# IC_Programmers.net
KiCad netlist of a schematic drawn in Altium Designer
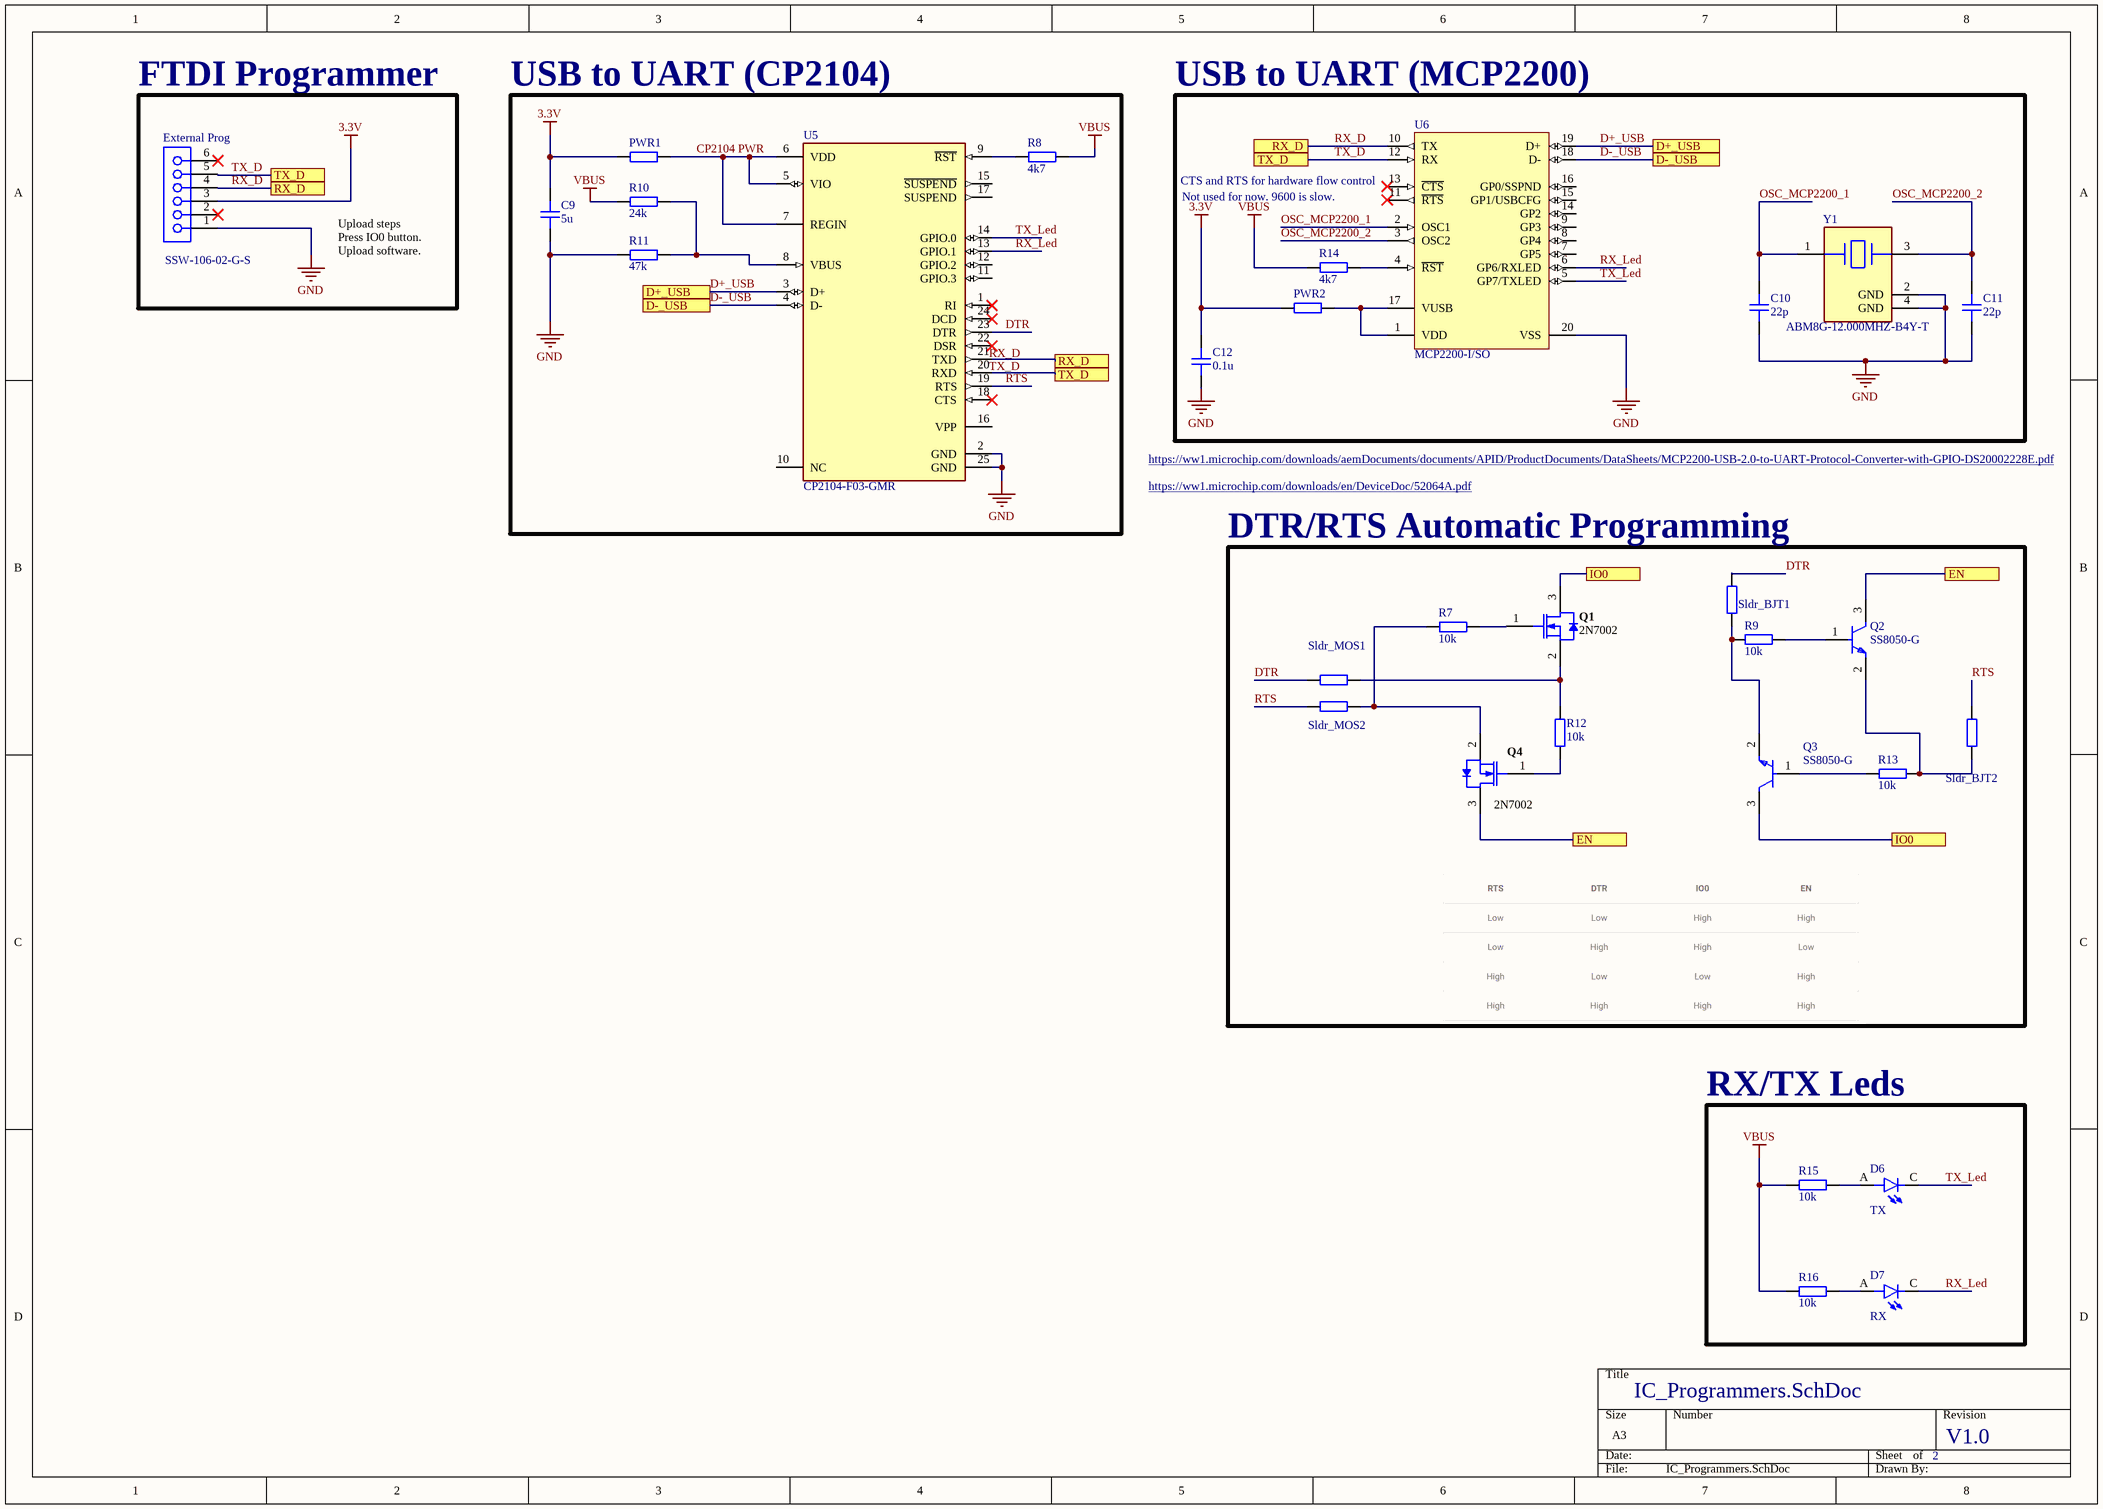
[diagram p0: IC_Programmers.SchDoc]

(export (version "E")
  (design (tool "Eeschema 10.0.6"))
  (components
    (comp (ref "C9")
      (value "5u")
      (footprint "CAP_1206")
      (description "Capacitor SMD 1206 50V")
      (libsource (lib "Schem_Lib_DaanHeetkamp.") (part "CAP_1206_50V"))
    )
    (comp (ref "C10")
      (value "22p")
      (footprint "CAP_1206")
      (description "Capacitor SMD 1206 50V")
      (libsource (lib "Schem_Lib_DaanHeetkamp.") (part "CAP_1206_50V"))
    )
    (comp (ref "C11")
      (value "22p")
      (footprint "CAP_1206")
      (description "Capacitor SMD 1206 50V")
      (libsource (lib "Schem_Lib_DaanHeetkamp.") (part "CAP_1206_50V"))
    )
    (comp (ref "C12")
      (value "0.1u")
      (footprint "CAP_1206")
      (description "Capacitor SMD 1206 50V")
      (libsource (lib "Schem_Lib_DaanHeetkamp.") (part "CAP_1206_50V"))
    )
    (comp (ref "D6")
      (value "TX")
      (footprint "PCB_Lib_DaanHeetkamp:LED_1206")
      (description "Yellow 587nm LED Indication - Discrete 2V 1206 _3216 Metric_")
      (fields (field (name "MF") "Lite-On Inc.") (field (name "MP") "LTST-C230KSKT"))
      (libsource (lib "Schem_Lib_DaanHeetkamp.") (part "LED - 1206"))
    )
    (comp (ref "D7")
      (value "RX")
      (footprint "PCB_Lib_DaanHeetkamp:LED_1206")
      (description "Yellow 587nm LED Indication - Discrete 2V 1206 _3216 Metric_")
      (fields (field (name "MF") "Lite-On Inc.") (field (name "MP") "LTST-C230KSKT"))
      (libsource (lib "Schem_Lib_DaanHeetkamp.") (part "LED - 1206"))
    )
    (comp (ref "External Prog")
      (value "SSW-106-02-G-S")
      (footprint "SMTC-SSW-106-02-X-S")
      (description "SQ Post Socket, Through-hole, Vertical, -55 to 125 degC, 2.54mm Pitch, 6-Pin, Female, RoHS")
      (fields (field (name "MANUFACTURER") "Samtec"))
      (libsource (lib "Altium Content Vault") (part "SMTC-SSW-106-02-X-S-X"))
    )
    (comp (ref "PWR1")
      (value "Solder Pin CP2104")
      (footprint "RES_1206")
      (description "Resistor SMD 1206")
      (libsource (lib "Schem_Lib_DaanHeetkamp.") (part "RES_1206"))
    )
    (comp (ref "PWR2")
      (value "Solder MCP2200")
      (footprint "RES_1206")
      (description "Resistor SMD 1206")
      (libsource (lib "Schem_Lib_DaanHeetkamp.") (part "RES_1206"))
    )
    (comp (ref "Q1")
      (value "2N7002")
      (footprint "INF-PG-SOT23_M")
      (fields (field (name "MANUFACTURER") "Infineon"))
      (libsource (lib "Altium Content Vault") (part "INF-NDMOS-GSD-3"))
    )
    (comp (ref "Q2")
      (value "SS8050-G")
      (footprint "FP-SS8050-G-MFG")
      (description "NPN TRANSISTOR 1.5A 40V SOT-23 R")
      (libsource (lib "Altium Content Vault") (part "2a1388f82443b098dcd57d24ac7632d"))
    )
    (comp (ref "Q3")
      (value "SS8050-G")
      (footprint "FP-SS8050-G-MFG")
      (description "NPN TRANSISTOR 1.5A 40V SOT-23 R")
      (libsource (lib "Altium Content Vault") (part "2a1388f82443b098dcd57d24ac7632d"))
    )
    (comp (ref "Q4")
      (value "2N7002")
      (footprint "INF-PG-SOT23_M")
      (fields (field (name "MANUFACTURER") "Infineon"))
      (libsource (lib "Altium Content Vault") (part "INF-NDMOS-GSD-3"))
    )
    (comp (ref "R7")
      (value "10k")
      (footprint "RES_1206")
      (description "Resistor SMD 1206")
      (libsource (lib "Schem_Lib_DaanHeetkamp.") (part "RES_1206"))
    )
    (comp (ref "R8")
      (value "4k7")
      (footprint "RES_1206")
      (description "Resistor SMD 1206")
      (libsource (lib "Schem_Lib_DaanHeetkamp.") (part "RES_1206"))
    )
    (comp (ref "R9")
      (value "10k")
      (footprint "RES_1206")
      (description "Resistor SMD 1206")
      (libsource (lib "Schem_Lib_DaanHeetkamp.") (part "RES_1206"))
    )
    (comp (ref "R10")
      (value "24k")
      (footprint "RES_1206")
      (description "Resistor SMD 1206")
      (libsource (lib "Schem_Lib_DaanHeetkamp.") (part "RES_1206"))
    )
    (comp (ref "R11")
      (value "47k")
      (footprint "RES_1206")
      (description "Resistor SMD 1206")
      (libsource (lib "Schem_Lib_DaanHeetkamp.") (part "RES_1206"))
    )
    (comp (ref "R12")
      (value "10k")
      (footprint "RES_1206")
      (description "Resistor SMD 1206")
      (libsource (lib "Schem_Lib_DaanHeetkamp.") (part "RES_1206"))
    )
    (comp (ref "R13")
      (value "10k")
      (footprint "RES_1206")
      (description "Resistor SMD 1206")
      (libsource (lib "Schem_Lib_DaanHeetkamp.") (part "RES_1206"))
    )
    (comp (ref "R14")
      (value "4k7")
      (footprint "RES_1206")
      (description "Resistor SMD 1206")
      (libsource (lib "Schem_Lib_DaanHeetkamp.") (part "RES_1206"))
    )
    (comp (ref "R15")
      (value "10k")
      (footprint "RES_1206")
      (description "Resistor SMD 1206")
      (libsource (lib "Schem_Lib_DaanHeetkamp.") (part "RES_1206"))
    )
    (comp (ref "R16")
      (value "10k")
      (footprint "RES_1206")
      (description "Resistor SMD 1206")
      (libsource (lib "Schem_Lib_DaanHeetkamp.") (part "RES_1206"))
    )
    (comp (ref "Sldr_BJT1")
      (value "R0603")
      (footprint "RES_0603")
      (description "Resistor SMD 0603")
      (libsource (lib "Schem_Lib_DaanHeetkamp.") (part "RES_0603"))
    )
    (comp (ref "Sldr_BJT2")
      (value "R0603")
      (footprint "RES_0603")
      (description "Resistor SMD 0603")
      (libsource (lib "Schem_Lib_DaanHeetkamp.") (part "RES_0603"))
    )
    (comp (ref "Sldr_MOS1")
      (value "R0603")
      (footprint "RES_0603")
      (description "Resistor SMD 0603")
      (libsource (lib "Schem_Lib_DaanHeetkamp.") (part "RES_0603"))
    )
    (comp (ref "Sldr_MOS2")
      (value "R0603")
      (footprint "RES_0603")
      (description "Resistor SMD 0603")
      (libsource (lib "Schem_Lib_DaanHeetkamp.") (part "RES_0603"))
    )
    (comp (ref "U5")
      (value "CP2104-F03-GMR")
      (footprint "FP-CP2104-F03-GMR-MFG")
      (description "IC SGL USB-TO-UART BRIDGE 24QFN")
      (fields
        (field (name "OCTOPART") "https://octopart.com/cp2104-f03-gmr-silicon+labs-19668642")
        (field (name "MANUFACTURER") "Silicon Laboratories")
      )
      (libsource (lib "Altium Content Vault") (part "c264a613fa4ce846ece45e07ca4b292"))
    )
    (comp (ref "U6")
      (value "MCP2200-I/SO")
      (footprint "SOIC-SO20_M")
      (description "USB 2.0 to UART Protocol Converter with GPIO, 20-Pin SOIC, Industrial Temperature")
      (libsource (lib "Altium Content Vault") (part "COM-USB-MCP2200-20"))
    )
    (comp (ref "Y1")
      (value "ABM8G-12.000MHZ-B4Y-T")
      (footprint "FP-ABM8G-MFG")
      (description "Crystal 12MHz ±30ppm (Tol) ±30ppm (Stability) 10pF FUND 120Ω 4-Pin SMD T/R")
      (fields (field (name "TOLERANCE") "30ppm"))
      (libsource (lib "Altium Content Vault") (part "48e526d86b7f2615d98721063c72f49"))
    )
  )
  (nets
    (net (code "1") (name "/CP2104 PWR") (class "Default")
      (node (ref "PWR1") (pin "2") (pinfunction "2_2") (pintype "passive"))
      (node (ref "U5") (pin "5") (pinfunction "VIO_5") (pintype "bidirectional"))
      (node (ref "U5") (pin "6") (pinfunction "VDD_6") (pintype "power_in"))
      (node (ref "U5") (pin "7") (pinfunction "REGIN_7") (pintype "power_in"))
    )
    (net (code "2") (name "/D+_USB") (class "Default")
      (node (ref "U5") (pin "3") (pinfunction "D+_3") (pintype "bidirectional"))
      (node (ref "U6") (pin "19") (pinfunction "D+_19") (pintype "bidirectional"))
    )
    (net (code "3") (name "/D-_USB") (class "Default")
      (node (ref "U5") (pin "4") (pinfunction "D-_4") (pintype "bidirectional"))
      (node (ref "U6") (pin "18") (pinfunction "D-_18") (pintype "bidirectional"))
    )
    (net (code "4") (name "/DTR") (class "Default")
      (node (ref "Sldr_BJT1") (pin "2") (pinfunction "2_2") (pintype "passive"))
      (node (ref "Sldr_MOS1") (pin "2") (pinfunction "2_2") (pintype "passive"))
      (node (ref "U5") (pin "23") (pinfunction "DTR_23") (pintype "output"))
    )
    (net (code "5") (name "/EN") (class "Default")
      (node (ref "Q2") (pin "3") (pinfunction "C_3") (pintype "passive"))
      (node (ref "Q4") (pin "3") (pinfunction "DRAIN_3") (pintype "passive"))
    )
    (net (code "6") (name "/IO0") (class "Default")
      (node (ref "Q1") (pin "3") (pinfunction "DRAIN_3") (pintype "passive"))
      (node (ref "Q3") (pin "3") (pinfunction "C_3") (pintype "passive"))
    )
    (net (code "7") (name "/OSC_MCP2200_1") (class "Default")
      (node (ref "C10") (pin "2") (pinfunction "2_2") (pintype "passive"))
      (node (ref "U6") (pin "2") (pinfunction "OSC1_2") (pintype "input"))
      (node (ref "Y1") (pin "1") (pinfunction "1_1") (pintype "passive"))
    )
    (net (code "8") (name "/OSC_MCP2200_2") (class "Default")
      (node (ref "C11") (pin "2") (pinfunction "2_2") (pintype "passive"))
      (node (ref "U6") (pin "3") (pinfunction "OSC2_3") (pintype "output"))
      (node (ref "Y1") (pin "3") (pinfunction "3_3") (pintype "passive"))
    )
    (net (code "9") (name "/RTS") (class "Default")
      (node (ref "Sldr_BJT2") (pin "2") (pinfunction "2_2") (pintype "passive"))
      (node (ref "Sldr_MOS2") (pin "2") (pinfunction "2_2") (pintype "passive"))
      (node (ref "U5") (pin "19") (pinfunction "RTS_19") (pintype "output"))
    )
    (net (code "10") (name "/RX_D") (class "Default")
      (node (ref "External Prog") (pin "4") (pinfunction "4_4") (pintype "passive"))
      (node (ref "U5") (pin "21") (pinfunction "TXD_21") (pintype "output"))
      (node (ref "U6") (pin "10") (pinfunction "TX_10") (pintype "output"))
    )
    (net (code "11") (name "/RX_Led") (class "Default")
      (node (ref "D7") (pin "C") (pinfunction "C_C") (pintype "passive"))
      (node (ref "U5") (pin "13") (pinfunction "GPIO.1_13") (pintype "bidirectional"))
      (node (ref "U6") (pin "6") (pinfunction "GP6/RXLED_6") (pintype "bidirectional"))
    )
    (net (code "12") (name "/TX_D") (class "Default")
      (node (ref "External Prog") (pin "5") (pinfunction "5_5") (pintype "passive"))
      (node (ref "U5") (pin "20") (pinfunction "RXD_20") (pintype "input"))
      (node (ref "U6") (pin "12") (pinfunction "RX_12") (pintype "input"))
    )
    (net (code "13") (name "/TX_Led") (class "Default")
      (node (ref "D6") (pin "C") (pinfunction "C_C") (pintype "passive"))
      (node (ref "U5") (pin "14") (pinfunction "GPIO.0_14") (pintype "bidirectional"))
      (node (ref "U6") (pin "5") (pinfunction "GP7/TXLED_5") (pintype "bidirectional"))
    )
    (net (code "14") (name "3.3V") (class "Default")
      (node (ref "C12") (pin "2") (pinfunction "2_2") (pintype "passive"))
      (node (ref "C9") (pin "2") (pinfunction "2_2") (pintype "passive"))
      (node (ref "External Prog") (pin "3") (pinfunction "3_3") (pintype "passive"))
      (node (ref "PWR1") (pin "1") (pinfunction "1_1") (pintype "passive"))
      (node (ref "PWR2") (pin "1") (pinfunction "1_1") (pintype "passive"))
    )
    (net (code "15") (name "GND") (class "Default")
      (node (ref "C10") (pin "1") (pinfunction "1_1") (pintype "passive"))
      (node (ref "C11") (pin "1") (pinfunction "1_1") (pintype "passive"))
      (node (ref "C12") (pin "1") (pinfunction "1_1") (pintype "passive"))
      (node (ref "C9") (pin "1") (pinfunction "1_1") (pintype "passive"))
      (node (ref "External Prog") (pin "1") (pinfunction "1_1") (pintype "passive"))
      (node (ref "R11") (pin "1") (pinfunction "1_1") (pintype "passive"))
      (node (ref "U5") (pin "2") (pinfunction "GND_2") (pintype "power_in"))
      (node (ref "U5") (pin "25") (pinfunction "GND_25") (pintype "power_in"))
      (node (ref "U6") (pin "20") (pinfunction "VSS_20") (pintype "power_in"))
      (node (ref "Y1") (pin "2") (pinfunction "GND_2") (pintype "power_in"))
      (node (ref "Y1") (pin "4") (pinfunction "GND_4") (pintype "power_in"))
    )
    (net (code "16") (name "Net-(D6-PadA)") (class "Default")
      (node (ref "D6") (pin "A") (pinfunction "A_A") (pintype "passive"))
      (node (ref "R15") (pin "2") (pinfunction "2_2") (pintype "passive"))
    )
    (net (code "17") (name "Net-(D7-PadA)") (class "Default")
      (node (ref "D7") (pin "A") (pinfunction "A_A") (pintype "passive"))
      (node (ref "R16") (pin "2") (pinfunction "2_2") (pintype "passive"))
    )
    (net (code "18") (name "Net-(Q1-GATE)") (class "Default")
      (node (ref "Q1") (pin "1") (pinfunction "GATE_1") (pintype "passive"))
      (node (ref "R7") (pin "2") (pinfunction "2_2") (pintype "passive"))
    )
    (net (code "19") (name "Net-(Q1-SOURCE)") (class "Default")
      (node (ref "Q1") (pin "2") (pinfunction "SOURCE_2") (pintype "passive"))
      (node (ref "R12") (pin "1") (pinfunction "1_1") (pintype "passive"))
      (node (ref "Sldr_MOS1") (pin "1") (pinfunction "1_1") (pintype "passive"))
    )
    (net (code "20") (name "Net-(Q2-B)") (class "Default")
      (node (ref "Q2") (pin "1") (pinfunction "B_1") (pintype "passive"))
      (node (ref "R9") (pin "1") (pinfunction "1_1") (pintype "passive"))
    )
    (net (code "21") (name "Net-(Q2-E)") (class "Default")
      (node (ref "Q2") (pin "2") (pinfunction "E_2") (pintype "passive"))
      (node (ref "R13") (pin "2") (pinfunction "2_2") (pintype "passive"))
      (node (ref "Sldr_BJT2") (pin "1") (pinfunction "1_1") (pintype "passive"))
    )
    (net (code "22") (name "Net-(Q3-B)") (class "Default")
      (node (ref "Q3") (pin "1") (pinfunction "B_1") (pintype "passive"))
      (node (ref "R13") (pin "1") (pinfunction "1_1") (pintype "passive"))
    )
    (net (code "23") (name "Net-(Q3-E)") (class "Default")
      (node (ref "Q3") (pin "2") (pinfunction "E_2") (pintype "passive"))
      (node (ref "R9") (pin "2") (pinfunction "2_2") (pintype "passive"))
      (node (ref "Sldr_BJT1") (pin "1") (pinfunction "1_1") (pintype "passive"))
    )
    (net (code "24") (name "Net-(Q4-GATE)") (class "Default")
      (node (ref "Q4") (pin "1") (pinfunction "GATE_1") (pintype "passive"))
      (node (ref "R12") (pin "2") (pinfunction "2_2") (pintype "passive"))
    )
    (net (code "25") (name "Net-(Q4-SOURCE)") (class "Default")
      (node (ref "Q4") (pin "2") (pinfunction "SOURCE_2") (pintype "passive"))
      (node (ref "R7") (pin "1") (pinfunction "1_1") (pintype "passive"))
      (node (ref "Sldr_MOS2") (pin "1") (pinfunction "1_1") (pintype "passive"))
    )
    (net (code "26") (name "Net-(U5-VBUS)") (class "Default")
      (node (ref "R10") (pin "2") (pinfunction "2_2") (pintype "passive"))
      (node (ref "R11") (pin "2") (pinfunction "2_2") (pintype "passive"))
      (node (ref "U5") (pin "8") (pinfunction "VBUS_8") (pintype "input"))
    )
    (net (code "27") (name "Net-(U5-~{RST})") (class "Default")
      (node (ref "R8") (pin "2") (pinfunction "2_2") (pintype "passive"))
      (node (ref "U5") (pin "9") (pinfunction "~{RST}_9") (pintype "input"))
    )
    (net (code "28") (name "Net-(U6-VDD)") (class "Default")
      (node (ref "PWR2") (pin "2") (pinfunction "2_2") (pintype "passive"))
      (node (ref "U6") (pin "1") (pinfunction "VDD_1") (pintype "power_in"))
      (node (ref "U6") (pin "17") (pinfunction "VUSB_17") (pintype "power_in"))
    )
    (net (code "29") (name "Net-(U6-~{RST})") (class "Default")
      (node (ref "R14") (pin "2") (pinfunction "2_2") (pintype "passive"))
      (node (ref "U6") (pin "4") (pinfunction "~{RST}_4") (pintype "input"))
    )
    (net (code "30") (name "VBUS") (class "Default")
      (node (ref "R10") (pin "1") (pinfunction "1_1") (pintype "passive"))
      (node (ref "R14") (pin "1") (pinfunction "1_1") (pintype "passive"))
      (node (ref "R15") (pin "1") (pinfunction "1_1") (pintype "passive"))
      (node (ref "R16") (pin "1") (pinfunction "1_1") (pintype "passive"))
      (node (ref "R8") (pin "1") (pinfunction "1_1") (pintype "passive"))
    )
    (net (code "31") (name "unconnected-(External Prog-Pad2)") (class "Default")
      (node (ref "External Prog") (pin "2") (pinfunction "2_2") (pintype "passive+no_connect"))
    )
    (net (code "32") (name "unconnected-(External Prog-Pad6)") (class "Default")
      (node (ref "External Prog") (pin "6") (pinfunction "6_6") (pintype "passive+no_connect"))
    )
    (net (code "33") (name "unconnected-(U5-CTS-Pad18)") (class "Default")
      (node (ref "U5") (pin "18") (pinfunction "CTS_18") (pintype "input+no_connect"))
    )
    (net (code "34") (name "unconnected-(U5-DCD-Pad24)") (class "Default")
      (node (ref "U5") (pin "24") (pinfunction "DCD_24") (pintype "input+no_connect"))
    )
    (net (code "35") (name "unconnected-(U5-DSR-Pad22)") (class "Default")
      (node (ref "U5") (pin "22") (pinfunction "DSR_22") (pintype "input+no_connect"))
    )
    (net (code "36") (name "unconnected-(U5-GPIO.2-Pad12)") (class "Default")
      (node (ref "U5") (pin "12") (pinfunction "GPIO.2_12") (pintype "bidirectional"))
    )
    (net (code "37") (name "unconnected-(U5-GPIO.3-Pad11)") (class "Default")
      (node (ref "U5") (pin "11") (pinfunction "GPIO.3_11") (pintype "bidirectional"))
    )
    (net (code "38") (name "unconnected-(U5-NC-Pad10)") (class "Default")
      (node (ref "U5") (pin "10") (pinfunction "NC_10") (pintype "passive"))
    )
    (net (code "39") (name "unconnected-(U5-RI-Pad1)") (class "Default")
      (node (ref "U5") (pin "1") (pinfunction "RI_1") (pintype "input+no_connect"))
    )
    (net (code "40") (name "unconnected-(U5-SUSPEND-Pad17)") (class "Default")
      (node (ref "U5") (pin "17") (pinfunction "SUSPEND_17") (pintype "output"))
    )
    (net (code "41") (name "unconnected-(U5-VPP-Pad16)") (class "Default")
      (node (ref "U5") (pin "16") (pinfunction "VPP_16") (pintype "power_in"))
    )
    (net (code "42") (name "unconnected-(U5-~{SUSPEND}-Pad15)") (class "Default")
      (node (ref "U5") (pin "15") (pinfunction "~{SUSPEND}_15") (pintype "output"))
    )
    (net (code "43") (name "unconnected-(U6-GP0{slash}SSPND-Pad16)") (class "Default")
      (node (ref "U6") (pin "16") (pinfunction "GP0/SSPND_16") (pintype "bidirectional"))
    )
    (net (code "44") (name "unconnected-(U6-GP1{slash}USBCFG-Pad15)") (class "Default")
      (node (ref "U6") (pin "15") (pinfunction "GP1/USBCFG_15") (pintype "bidirectional"))
    )
    (net (code "45") (name "unconnected-(U6-GP2-Pad14)") (class "Default")
      (node (ref "U6") (pin "14") (pinfunction "GP2_14") (pintype "bidirectional"))
    )
    (net (code "46") (name "unconnected-(U6-GP3-Pad9)") (class "Default")
      (node (ref "U6") (pin "9") (pinfunction "GP3_9") (pintype "bidirectional"))
    )
    (net (code "47") (name "unconnected-(U6-GP4-Pad8)") (class "Default")
      (node (ref "U6") (pin "8") (pinfunction "GP4_8") (pintype "bidirectional"))
    )
    (net (code "48") (name "unconnected-(U6-GP5-Pad7)") (class "Default")
      (node (ref "U6") (pin "7") (pinfunction "GP5_7") (pintype "bidirectional"))
    )
    (net (code "49") (name "unconnected-(U6-~{CTS}-Pad13)") (class "Default")
      (node (ref "U6") (pin "13") (pinfunction "~{CTS}_13") (pintype "input+no_connect"))
    )
    (net (code "50") (name "unconnected-(U6-~{RTS}-Pad11)") (class "Default")
      (node (ref "U6") (pin "11") (pinfunction "~{RTS}_11") (pintype "output+no_connect"))
    )
  )
)
